# OSO-MISC-20-010.net
KiCad netlist of a schematic drawn in EAGLE
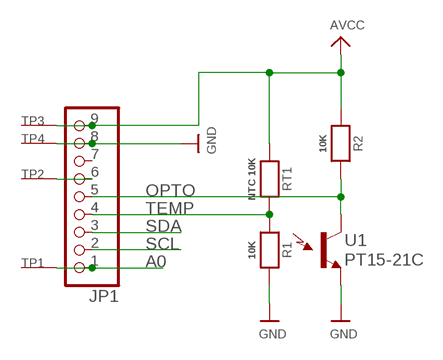
[diagram p0: schematic, sheet 1]

(export (version "E")
  (design (tool "Eeschema 10.0.6"))
  (components
    (comp (ref "JP1")
      (value "HEADER-1X9_JSTSH")
      (footprint "eagle-import:JST_SH9")
      (libsource (lib "eagle-import") (part "HEADER-1X9_JSTSH"))
    )
    (comp (ref "R1")
      (value "10K")
      (footprint "eagle-import:0805-NO")
      (libsource (lib "eagle-import") (part "RESISTOR0805_NOOUTLINE"))
    )
    (comp (ref "R2")
      (value "10K")
      (footprint "eagle-import:0805-NO")
      (libsource (lib "eagle-import") (part "RESISTOR0805_NOOUTLINE"))
    )
    (comp (ref "RT1")
      (value "NTC 10K")
      (footprint "eagle-import:0805-NO")
      (libsource (lib "eagle-import") (part "RESISTOR0805_NOOUTLINE"))
    )
    (comp (ref "TP1")
      (value "SEWTAP0.5IN")
      (footprint "eagle-import:SEWINGTAP_0.5")
      (libsource (lib "eagle-import") (part "SEWTAP0.5IN"))
    )
    (comp (ref "TP2")
      (value "SEWTAP0.5IN")
      (footprint "eagle-import:SEWINGTAP_0.5")
      (libsource (lib "eagle-import") (part "SEWTAP0.5IN"))
    )
    (comp (ref "TP3")
      (value "SEWTAP0.5IN")
      (footprint "eagle-import:SEWINGTAP_0.5")
      (libsource (lib "eagle-import") (part "SEWTAP0.5IN"))
    )
    (comp (ref "TP4")
      (value "SEWTAP0.5IN")
      (footprint "eagle-import:SEWINGTAP_0.5")
      (libsource (lib "eagle-import") (part "SEWTAP0.5IN"))
    )
    (comp (ref "U1")
      (value "PT15-21C")
      (footprint "eagle-import:LED-1206")
      (libsource (lib "eagle-import") (part "LIGHT_SENSOR1206"))
    )
  )
  (nets
    (net (code "1") (name "/A0") (class "Default")
      (node (ref "JP1") (pin "1") (pinfunction "1_1") (pintype "passive"))
      (node (ref "TP1") (pin "TAP") (pinfunction "SEW_TAP") (pintype "bidirectional"))
    )
    (net (code "2") (name "/OPTO") (class "Default")
      (node (ref "JP1") (pin "5") (pinfunction "5_5") (pintype "passive"))
      (node (ref "R2") (pin "2") (pinfunction "2_2") (pintype "passive"))
      (node (ref "U1") (pin "A") (pinfunction "C1_A") (pintype "passive"))
    )
    (net (code "3") (name "/SCL") (class "Default")
      (node (ref "JP1") (pin "2") (pinfunction "2_2") (pintype "passive"))
    )
    (net (code "4") (name "/SDA") (class "Default")
      (node (ref "JP1") (pin "3") (pinfunction "3_3") (pintype "passive"))
    )
    (net (code "5") (name "/TEMP") (class "Default")
      (node (ref "JP1") (pin "4") (pinfunction "4_4") (pintype "passive"))
      (node (ref "R1") (pin "1") (pinfunction "1_1") (pintype "passive"))
      (node (ref "RT1") (pin "2") (pinfunction "2_2") (pintype "passive"))
    )
    (net (code "6") (name "AVCC") (class "Default")
      (node (ref "JP1") (pin "9") (pinfunction "9_9") (pintype "passive"))
      (node (ref "R2") (pin "1") (pinfunction "1_1") (pintype "passive"))
      (node (ref "RT1") (pin "1") (pinfunction "1_1") (pintype "passive"))
      (node (ref "TP3") (pin "TAP") (pinfunction "SEW_TAP") (pintype "bidirectional"))
    )
    (net (code "7") (name "GND") (class "Default")
      (node (ref "JP1") (pin "8") (pinfunction "8_8") (pintype "passive"))
      (node (ref "R1") (pin "2") (pinfunction "2_2") (pintype "passive"))
      (node (ref "TP4") (pin "TAP") (pinfunction "SEW_TAP") (pintype "bidirectional"))
      (node (ref "U1") (pin "C") (pinfunction "E1_C") (pintype "passive"))
    )
    (net (code "8") (name "Net-(TP2-SEW)") (class "Default")
      (node (ref "JP1") (pin "6") (pinfunction "6_6") (pintype "passive"))
      (node (ref "TP2") (pin "TAP") (pinfunction "SEW_TAP") (pintype "bidirectional"))
    )
    (net (code "9") (name "unconnected-(JP1-Pad7)") (class "Default")
      (node (ref "JP1") (pin "7") (pinfunction "7_7") (pintype "passive"))
    )
  )
)
